# 00-SURGE_PROTECT.net
KiCad netlist of a schematic drawn in Altium Designer
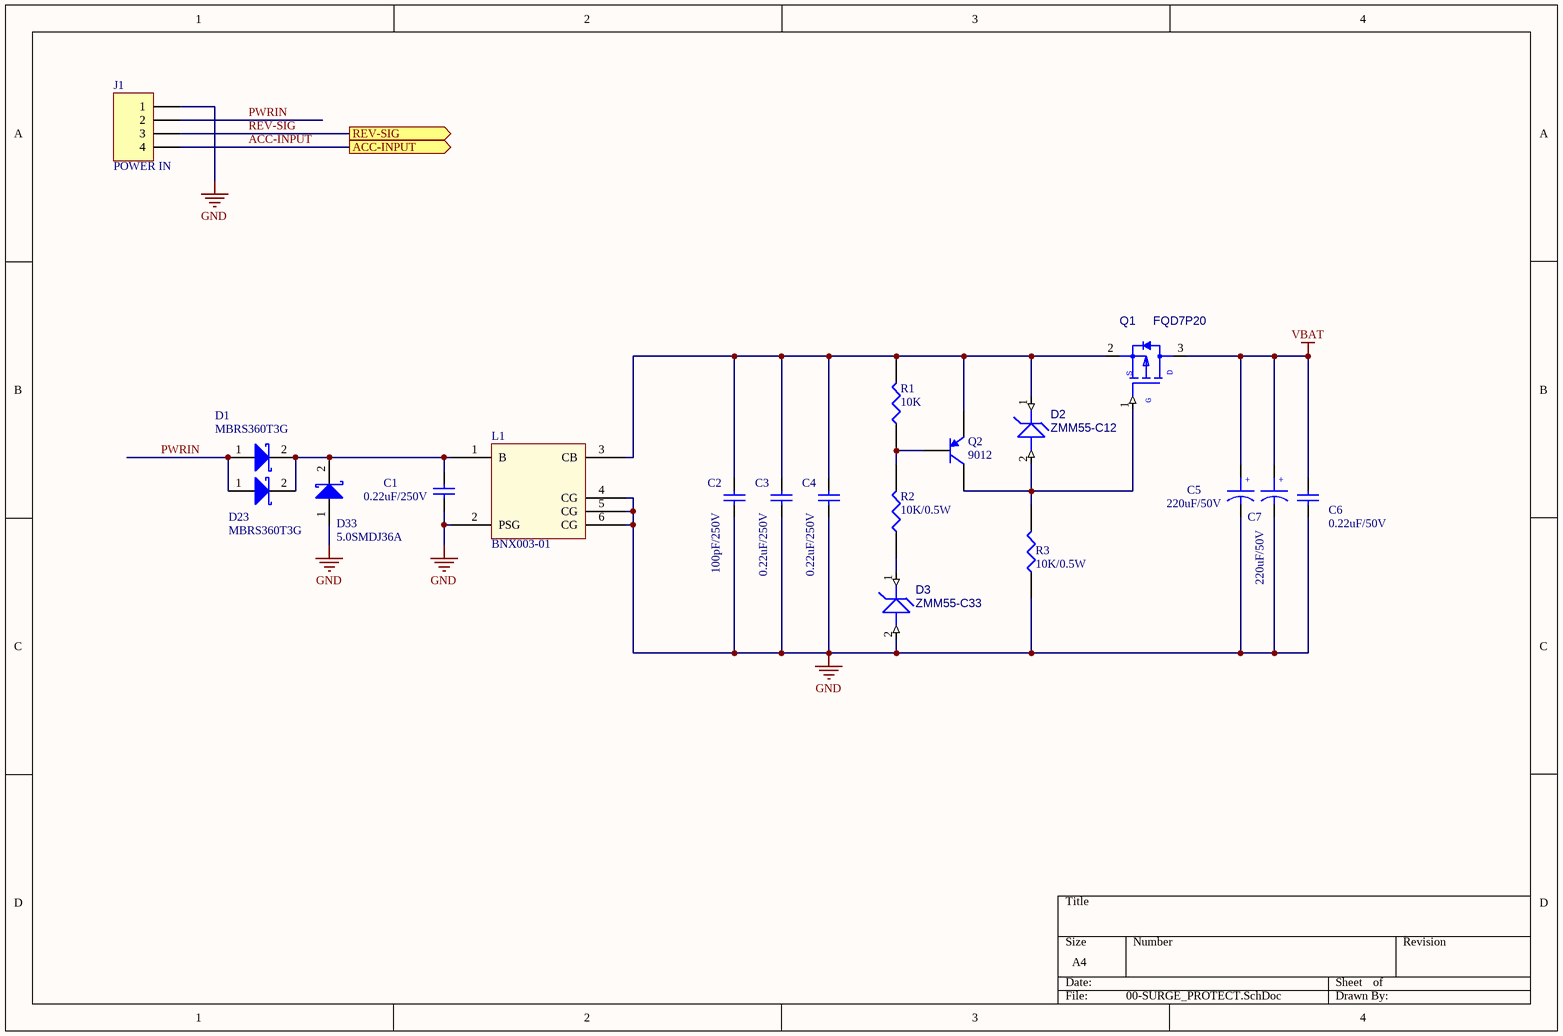
[diagram p0: 00-SURGE_PROTECT.SchDoc]

(export (version "E")
  (design (tool "Eeschema 10.0.6"))
  (components
    (comp (ref "C1")
      (value "0.22uF/250V")
      (footprint "1210")
      (description "Capacitor")
      (fields (field (name "PUBLISHER") "Altium Limited"))
      (libsource (lib "Miscellaneous Devices") (part "Cap"))
    )
    (comp (ref "C2")
      (value "100pF/250V")
      (footprint "0805")
      (description "Capacitor")
      (fields (field (name "PUBLISHER") "Altium Limited"))
      (libsource (lib "Miscellaneous Devices") (part "Cap"))
    )
    (comp (ref "C3")
      (value "0.22uF/250V")
      (footprint "1210")
      (description "Capacitor")
      (fields (field (name "PUBLISHER") "Altium Limited"))
      (libsource (lib "Miscellaneous Devices") (part "Cap"))
    )
    (comp (ref "C4")
      (value "0.22uF/250V")
      (footprint "1210")
      (description "Capacitor")
      (fields (field (name "PUBLISHER") "Altium Limited"))
      (libsource (lib "Miscellaneous Devices") (part "Cap"))
    )
    (comp (ref "C5") (value "220uF/50V") (footprint "DL-10*10.5") (libsource (lib "*") (part "CAP WP")))
    (comp (ref "C6")
      (value "0.22uF/50V")
      (footprint "0603")
      (description "Capacitor")
      (fields (field (name "PUBLISHER") "Altium Limited"))
      (libsource (lib "Miscellaneous Devices") (part "Cap"))
    )
    (comp (ref "C7") (value "220uF/50V") (footprint "DL-10*10.5") (libsource (lib "*") (part "CAP WP")))
    (comp (ref "D1")
      (value "MBRS360T3G")
      (footprint "SMC")
      (description "Schottky Rectifier")
      (libsource (lib "Miscellaneous Devices") (part "Diode 11DQ03"))
    )
    (comp (ref "D2")
      (value "ZMM55-C12")
      (footprint "MINI-MELF")
      (libsource (lib "*") (part "MMGZ5231BPTLL34"))
    )
    (comp (ref "D3")
      (value "ZMM55-C33")
      (footprint "MINI-MELF")
      (libsource (lib "*") (part "MMGZ5231BPTLL34"))
    )
    (comp (ref "D23")
      (value "MBRS360T3G")
      (footprint "SMC")
      (description "Schottky Rectifier")
      (libsource (lib "Miscellaneous Devices") (part "Diode 11DQ03"))
    )
    (comp (ref "D33")
      (value "5.0SMDJ36A")
      (footprint "SMC")
      (description "Schottky Rectifier")
      (libsource (lib "Miscellaneous Devices") (part "Diode 11DQ03"))
    )
    (comp (ref "J1")
      (value "POWER IN")
      (footprint "3030WR-S-2*2P")
      (description "Header, 4-Pin")
      (fields (field (name "PUBLISHER") "Altium Limited"))
      (libsource (lib "Miscellaneous Connectors") (part "Header 4"))
    )
    (comp (ref "L1")
      (value "BNX003-01")
      (footprint "BNX002-001")
      (libsource (lib "Schlib") (part "BNX002-01"))
    )
    (comp (ref "Q1")
      (value "FQD7P20")
      (footprint "FQD7P20")
      (fields (field (name "PART NUMBER") "SB934010010"))
      (libsource (lib "*") (part "AO3401L_SOT23-3_0"))
    )
    (comp (ref "Q2")
      (value "9012")
      (footprint "NPN")
      (description "PNP Bipolar Transistor")
      (fields (field (name "PUBLISHER") "Altium Limited"))
      (libsource (lib "Miscellaneous Devices") (part "PNP"))
    )
    (comp (ref "R1") (value "10K") (footprint "0402") (libsource (lib "*") (part "RES1")))
    (comp (ref "R2") (value "10K/0.5W") (footprint "1812") (libsource (lib "*") (part "RES1")))
    (comp (ref "R3") (value "10K/0.5W") (footprint "1812") (libsource (lib "*") (part "RES1")))
  )
  (nets
    (net (code "1") (name "/ACC-INPUT") (class "Default")
      (node (ref "J1") (pin "4") (pinfunction "4_4") (pintype "passive"))
    )
    (net (code "2") (name "/PWRIN") (class "Default")
      (node (ref "D1") (pin "1") (pinfunction "A_1") (pintype "passive"))
      (node (ref "D23") (pin "1") (pinfunction "A_1") (pintype "passive"))
      (node (ref "J1") (pin "2") (pinfunction "2_2") (pintype "passive"))
    )
    (net (code "3") (name "/REV-SIG") (class "Default")
      (node (ref "J1") (pin "3") (pinfunction "3_3") (pintype "passive"))
    )
    (net (code "4") (name "GND") (class "Default")
      (node (ref "C1") (pin "2") (pinfunction "2_2") (pintype "passive"))
      (node (ref "C2") (pin "2") (pinfunction "2_2") (pintype "passive"))
      (node (ref "C3") (pin "2") (pinfunction "2_2") (pintype "passive"))
      (node (ref "C4") (pin "2") (pinfunction "2_2") (pintype "passive"))
      (node (ref "C5") (pin "2") (pinfunction "2_2") (pintype "passive"))
      (node (ref "C6") (pin "2") (pinfunction "2_2") (pintype "passive"))
      (node (ref "C7") (pin "2") (pinfunction "2_2") (pintype "passive"))
      (node (ref "D3") (pin "2") (pinfunction "2_2") (pintype "input"))
      (node (ref "D33") (pin "1") (pinfunction "A_1") (pintype "passive"))
      (node (ref "J1") (pin "1") (pinfunction "1_1") (pintype "passive"))
      (node (ref "L1") (pin "2") (pinfunction "PSG_2") (pintype "passive"))
      (node (ref "L1") (pin "4") (pinfunction "CG_4") (pintype "passive"))
      (node (ref "L1") (pin "5") (pinfunction "CG_5") (pintype "passive"))
      (node (ref "L1") (pin "6") (pinfunction "CG_6") (pintype "passive"))
      (node (ref "R3") (pin "1") (pinfunction "1_1") (pintype "passive"))
    )
    (net (code "5") (name "Net-(D1-K)") (class "Default")
      (node (ref "C1") (pin "1") (pinfunction "1_1") (pintype "passive"))
      (node (ref "D1") (pin "2") (pinfunction "K_2") (pintype "passive"))
      (node (ref "D23") (pin "2") (pinfunction "K_2") (pintype "passive"))
      (node (ref "D33") (pin "2") (pinfunction "K_2") (pintype "passive"))
      (node (ref "L1") (pin "1") (pinfunction "B_1") (pintype "passive"))
    )
    (net (code "6") (name "Net-(D3-Pad1)") (class "Default")
      (node (ref "D3") (pin "1") (pinfunction "1_1") (pintype "input"))
      (node (ref "R2") (pin "1") (pinfunction "1_1") (pintype "passive"))
    )
    (net (code "7") (name "Net-(L1-CB)") (class "Default")
      (node (ref "C2") (pin "1") (pinfunction "1_1") (pintype "passive"))
      (node (ref "C3") (pin "1") (pinfunction "1_1") (pintype "passive"))
      (node (ref "C4") (pin "1") (pinfunction "1_1") (pintype "passive"))
      (node (ref "D2") (pin "1") (pinfunction "1_1") (pintype "input"))
      (node (ref "L1") (pin "3") (pinfunction "CB_3") (pintype "passive"))
      (node (ref "Q1") (pin "2") (pinfunction "S_2") (pintype "passive"))
      (node (ref "Q2") (pin "3") (pinfunction "E_3") (pintype "passive"))
      (node (ref "R1") (pin "2") (pinfunction "2_2") (pintype "passive"))
    )
    (net (code "8") (name "Net-(Q1-G)") (class "Default")
      (node (ref "D2") (pin "2") (pinfunction "2_2") (pintype "input"))
      (node (ref "Q1") (pin "1") (pinfunction "G_1") (pintype "input"))
      (node (ref "Q2") (pin "1") (pinfunction "C_1") (pintype "passive"))
      (node (ref "R3") (pin "2") (pinfunction "2_2") (pintype "passive"))
    )
    (net (code "9") (name "Net-(Q2-B)") (class "Default")
      (node (ref "Q2") (pin "2") (pinfunction "B_2") (pintype "passive"))
      (node (ref "R1") (pin "1") (pinfunction "1_1") (pintype "passive"))
      (node (ref "R2") (pin "2") (pinfunction "2_2") (pintype "passive"))
    )
    (net (code "10") (name "VBAT") (class "Default")
      (node (ref "C5") (pin "1") (pinfunction "1_1") (pintype "passive"))
      (node (ref "C6") (pin "1") (pinfunction "1_1") (pintype "passive"))
      (node (ref "C7") (pin "1") (pinfunction "1_1") (pintype "passive"))
      (node (ref "Q1") (pin "3") (pinfunction "D_3") (pintype "passive"))
    )
  )
)
